# Underglow.net
KiCad netlist of a schematic drawn in Altium Designer
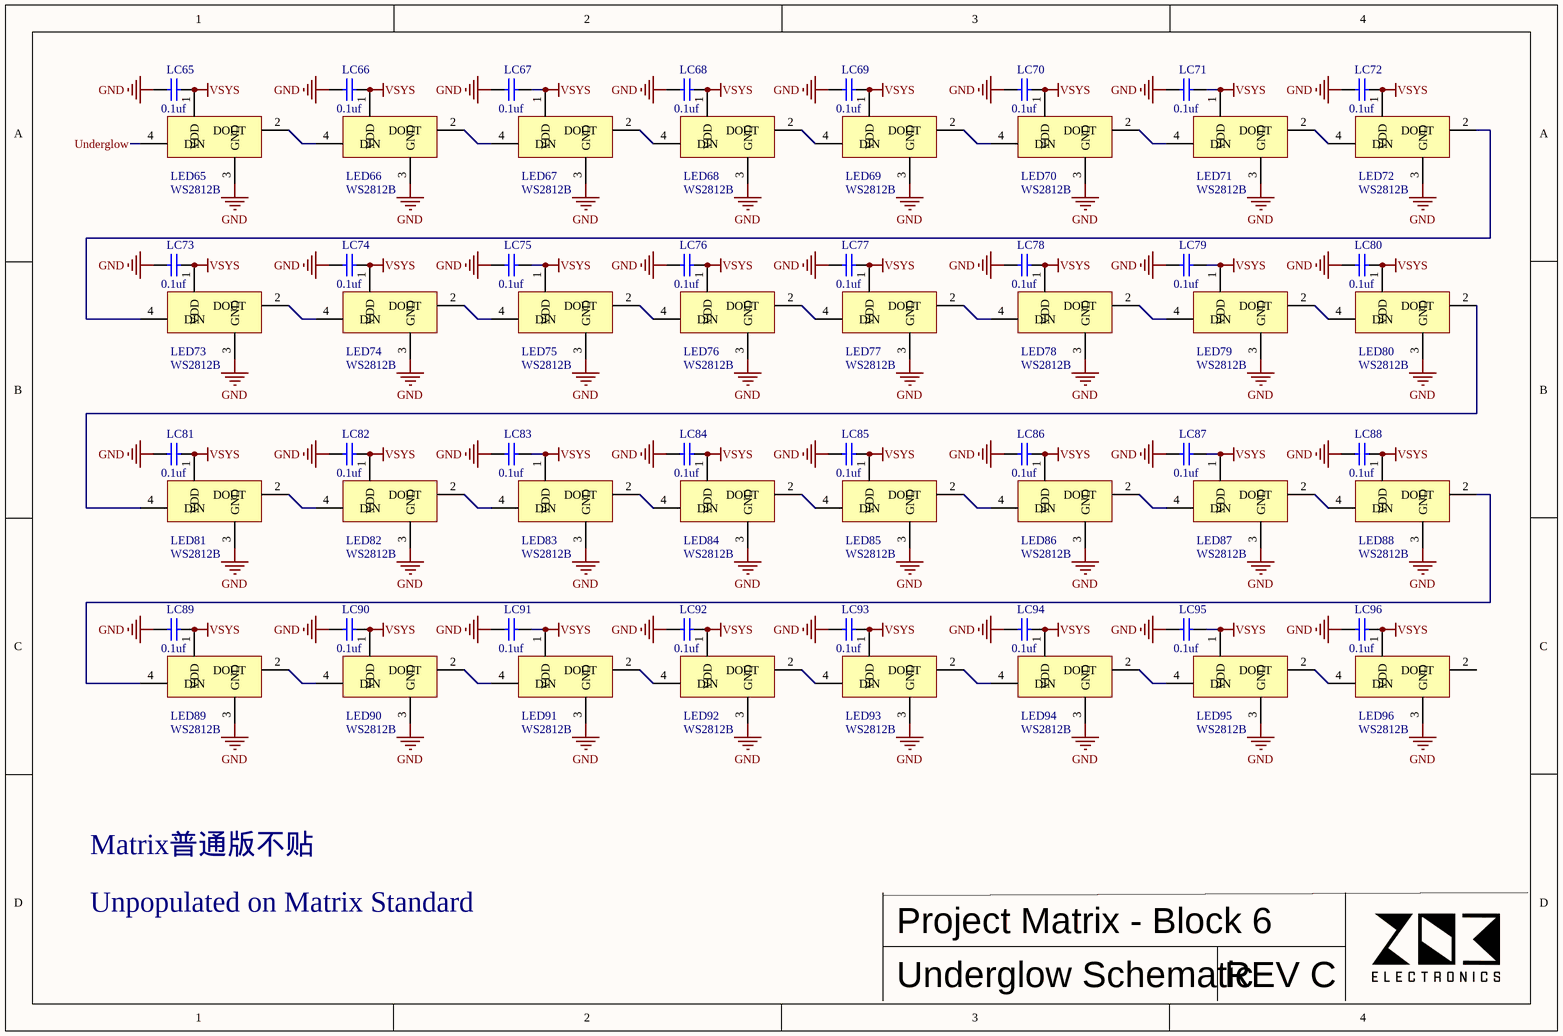
[diagram p0: Underglow.SchDoc]

(export (version "E")
  (design (tool "Eeschema 10.0.6"))
  (components
    (comp (ref "LC65")
      (value "0.1uf")
      (footprint "0603 CAP")
      (description "Capacitor (Semiconductor SIM Model)")
      (fields (field (name "Comment") "Cap Semi") (field (name "PUBLISHER") "Altium Limited"))
      (libsource (lib "Miscellaneous Devices") (part "Cap Semi"))
    )
    (comp (ref "LC66")
      (value "0.1uf")
      (footprint "0603 CAP")
      (description "Capacitor (Semiconductor SIM Model)")
      (fields (field (name "Comment") "Cap Semi") (field (name "PUBLISHER") "Altium Limited"))
      (libsource (lib "Miscellaneous Devices") (part "Cap Semi"))
    )
    (comp (ref "LC67")
      (value "0.1uf")
      (footprint "0603 CAP")
      (description "Capacitor (Semiconductor SIM Model)")
      (fields (field (name "Comment") "Cap Semi") (field (name "PUBLISHER") "Altium Limited"))
      (libsource (lib "Miscellaneous Devices") (part "Cap Semi"))
    )
    (comp (ref "LC68")
      (value "0.1uf")
      (footprint "0603 CAP")
      (description "Capacitor (Semiconductor SIM Model)")
      (fields (field (name "Comment") "Cap Semi") (field (name "PUBLISHER") "Altium Limited"))
      (libsource (lib "Miscellaneous Devices") (part "Cap Semi"))
    )
    (comp (ref "LC69")
      (value "0.1uf")
      (footprint "0603 CAP")
      (description "Capacitor (Semiconductor SIM Model)")
      (fields (field (name "Comment") "Cap Semi") (field (name "PUBLISHER") "Altium Limited"))
      (libsource (lib "Miscellaneous Devices") (part "Cap Semi"))
    )
    (comp (ref "LC70")
      (value "0.1uf")
      (footprint "0603 CAP")
      (description "Capacitor (Semiconductor SIM Model)")
      (fields (field (name "Comment") "Cap Semi") (field (name "PUBLISHER") "Altium Limited"))
      (libsource (lib "Miscellaneous Devices") (part "Cap Semi"))
    )
    (comp (ref "LC71")
      (value "0.1uf")
      (footprint "0603 CAP")
      (description "Capacitor (Semiconductor SIM Model)")
      (fields (field (name "Comment") "Cap Semi") (field (name "PUBLISHER") "Altium Limited"))
      (libsource (lib "Miscellaneous Devices") (part "Cap Semi"))
    )
    (comp (ref "LC72")
      (value "0.1uf")
      (footprint "0603 CAP")
      (description "Capacitor (Semiconductor SIM Model)")
      (fields (field (name "Comment") "Cap Semi") (field (name "PUBLISHER") "Altium Limited"))
      (libsource (lib "Miscellaneous Devices") (part "Cap Semi"))
    )
    (comp (ref "LC73")
      (value "0.1uf")
      (footprint "0603 CAP")
      (description "Capacitor (Semiconductor SIM Model)")
      (fields (field (name "Comment") "Cap Semi") (field (name "PUBLISHER") "Altium Limited"))
      (libsource (lib "Miscellaneous Devices") (part "Cap Semi"))
    )
    (comp (ref "LC74")
      (value "0.1uf")
      (footprint "0603 CAP")
      (description "Capacitor (Semiconductor SIM Model)")
      (fields (field (name "Comment") "Cap Semi") (field (name "PUBLISHER") "Altium Limited"))
      (libsource (lib "Miscellaneous Devices") (part "Cap Semi"))
    )
    (comp (ref "LC75")
      (value "0.1uf")
      (footprint "0603 CAP")
      (description "Capacitor (Semiconductor SIM Model)")
      (fields (field (name "Comment") "Cap Semi") (field (name "PUBLISHER") "Altium Limited"))
      (libsource (lib "Miscellaneous Devices") (part "Cap Semi"))
    )
    (comp (ref "LC76")
      (value "0.1uf")
      (footprint "0603 CAP")
      (description "Capacitor (Semiconductor SIM Model)")
      (fields (field (name "Comment") "Cap Semi") (field (name "PUBLISHER") "Altium Limited"))
      (libsource (lib "Miscellaneous Devices") (part "Cap Semi"))
    )
    (comp (ref "LC77")
      (value "0.1uf")
      (footprint "0603 CAP")
      (description "Capacitor (Semiconductor SIM Model)")
      (fields (field (name "Comment") "Cap Semi") (field (name "PUBLISHER") "Altium Limited"))
      (libsource (lib "Miscellaneous Devices") (part "Cap Semi"))
    )
    (comp (ref "LC78")
      (value "0.1uf")
      (footprint "0603 CAP")
      (description "Capacitor (Semiconductor SIM Model)")
      (fields (field (name "Comment") "Cap Semi") (field (name "PUBLISHER") "Altium Limited"))
      (libsource (lib "Miscellaneous Devices") (part "Cap Semi"))
    )
    (comp (ref "LC79")
      (value "0.1uf")
      (footprint "0603 CAP")
      (description "Capacitor (Semiconductor SIM Model)")
      (fields (field (name "Comment") "Cap Semi") (field (name "PUBLISHER") "Altium Limited"))
      (libsource (lib "Miscellaneous Devices") (part "Cap Semi"))
    )
    (comp (ref "LC80")
      (value "0.1uf")
      (footprint "0603 CAP")
      (description "Capacitor (Semiconductor SIM Model)")
      (fields (field (name "Comment") "Cap Semi") (field (name "PUBLISHER") "Altium Limited"))
      (libsource (lib "Miscellaneous Devices") (part "Cap Semi"))
    )
    (comp (ref "LC81")
      (value "0.1uf")
      (footprint "0603 CAP")
      (description "Capacitor (Semiconductor SIM Model)")
      (fields (field (name "Comment") "Cap Semi") (field (name "PUBLISHER") "Altium Limited"))
      (libsource (lib "Miscellaneous Devices") (part "Cap Semi"))
    )
    (comp (ref "LC82")
      (value "0.1uf")
      (footprint "0603 CAP")
      (description "Capacitor (Semiconductor SIM Model)")
      (fields (field (name "Comment") "Cap Semi") (field (name "PUBLISHER") "Altium Limited"))
      (libsource (lib "Miscellaneous Devices") (part "Cap Semi"))
    )
    (comp (ref "LC83")
      (value "0.1uf")
      (footprint "0603 CAP")
      (description "Capacitor (Semiconductor SIM Model)")
      (fields (field (name "Comment") "Cap Semi") (field (name "PUBLISHER") "Altium Limited"))
      (libsource (lib "Miscellaneous Devices") (part "Cap Semi"))
    )
    (comp (ref "LC84")
      (value "0.1uf")
      (footprint "0603 CAP")
      (description "Capacitor (Semiconductor SIM Model)")
      (fields (field (name "Comment") "Cap Semi") (field (name "PUBLISHER") "Altium Limited"))
      (libsource (lib "Miscellaneous Devices") (part "Cap Semi"))
    )
    (comp (ref "LC85")
      (value "0.1uf")
      (footprint "0603 CAP")
      (description "Capacitor (Semiconductor SIM Model)")
      (fields (field (name "Comment") "Cap Semi") (field (name "PUBLISHER") "Altium Limited"))
      (libsource (lib "Miscellaneous Devices") (part "Cap Semi"))
    )
    (comp (ref "LC86")
      (value "0.1uf")
      (footprint "0603 CAP")
      (description "Capacitor (Semiconductor SIM Model)")
      (fields (field (name "Comment") "Cap Semi") (field (name "PUBLISHER") "Altium Limited"))
      (libsource (lib "Miscellaneous Devices") (part "Cap Semi"))
    )
    (comp (ref "LC87")
      (value "0.1uf")
      (footprint "0603 CAP")
      (description "Capacitor (Semiconductor SIM Model)")
      (fields (field (name "Comment") "Cap Semi") (field (name "PUBLISHER") "Altium Limited"))
      (libsource (lib "Miscellaneous Devices") (part "Cap Semi"))
    )
    (comp (ref "LC88")
      (value "0.1uf")
      (footprint "0603 CAP")
      (description "Capacitor (Semiconductor SIM Model)")
      (fields (field (name "Comment") "Cap Semi") (field (name "PUBLISHER") "Altium Limited"))
      (libsource (lib "Miscellaneous Devices") (part "Cap Semi"))
    )
    (comp (ref "LC89")
      (value "0.1uf")
      (footprint "0603 CAP")
      (description "Capacitor (Semiconductor SIM Model)")
      (fields (field (name "Comment") "Cap Semi") (field (name "PUBLISHER") "Altium Limited"))
      (libsource (lib "Miscellaneous Devices") (part "Cap Semi"))
    )
    (comp (ref "LC90")
      (value "0.1uf")
      (footprint "0603 CAP")
      (description "Capacitor (Semiconductor SIM Model)")
      (fields (field (name "Comment") "Cap Semi") (field (name "PUBLISHER") "Altium Limited"))
      (libsource (lib "Miscellaneous Devices") (part "Cap Semi"))
    )
    (comp (ref "LC91")
      (value "0.1uf")
      (footprint "0603 CAP")
      (description "Capacitor (Semiconductor SIM Model)")
      (fields (field (name "Comment") "Cap Semi") (field (name "PUBLISHER") "Altium Limited"))
      (libsource (lib "Miscellaneous Devices") (part "Cap Semi"))
    )
    (comp (ref "LC92")
      (value "0.1uf")
      (footprint "0603 CAP")
      (description "Capacitor (Semiconductor SIM Model)")
      (fields (field (name "Comment") "Cap Semi") (field (name "PUBLISHER") "Altium Limited"))
      (libsource (lib "Miscellaneous Devices") (part "Cap Semi"))
    )
    (comp (ref "LC93")
      (value "0.1uf")
      (footprint "0603 CAP")
      (description "Capacitor (Semiconductor SIM Model)")
      (fields (field (name "Comment") "Cap Semi") (field (name "PUBLISHER") "Altium Limited"))
      (libsource (lib "Miscellaneous Devices") (part "Cap Semi"))
    )
    (comp (ref "LC94")
      (value "0.1uf")
      (footprint "0603 CAP")
      (description "Capacitor (Semiconductor SIM Model)")
      (fields (field (name "Comment") "Cap Semi") (field (name "PUBLISHER") "Altium Limited"))
      (libsource (lib "Miscellaneous Devices") (part "Cap Semi"))
    )
    (comp (ref "LC95")
      (value "0.1uf")
      (footprint "0603 CAP")
      (description "Capacitor (Semiconductor SIM Model)")
      (fields (field (name "Comment") "Cap Semi") (field (name "PUBLISHER") "Altium Limited"))
      (libsource (lib "Miscellaneous Devices") (part "Cap Semi"))
    )
    (comp (ref "LC96")
      (value "0.1uf")
      (footprint "0603 CAP")
      (description "Capacitor (Semiconductor SIM Model)")
      (fields (field (name "Comment") "Cap Semi") (field (name "PUBLISHER") "Altium Limited"))
      (libsource (lib "Miscellaneous Devices") (part "Cap Semi"))
    )
    (comp (ref "LED65")
      (value "WS2812B")
      (footprint "3210 LED")
      (description "3535")
      (libsource (lib "203") (part "WS2812B"))
    )
    (comp (ref "LED66")
      (value "WS2812B")
      (footprint "3210 LED")
      (description "3535")
      (libsource (lib "203") (part "WS2812B"))
    )
    (comp (ref "LED67")
      (value "WS2812B")
      (footprint "3210 LED")
      (description "3535")
      (libsource (lib "203") (part "WS2812B"))
    )
    (comp (ref "LED68")
      (value "WS2812B")
      (footprint "3210 LED")
      (description "3535")
      (libsource (lib "203") (part "WS2812B"))
    )
    (comp (ref "LED69")
      (value "WS2812B")
      (footprint "3210 LED")
      (description "3535")
      (libsource (lib "203") (part "WS2812B"))
    )
    (comp (ref "LED70")
      (value "WS2812B")
      (footprint "3210 LED")
      (description "3535")
      (libsource (lib "203") (part "WS2812B"))
    )
    (comp (ref "LED71")
      (value "WS2812B")
      (footprint "3210 LED")
      (description "3535")
      (libsource (lib "203") (part "WS2812B"))
    )
    (comp (ref "LED72")
      (value "WS2812B")
      (footprint "3210 LED")
      (description "3535")
      (libsource (lib "203") (part "WS2812B"))
    )
    (comp (ref "LED73")
      (value "WS2812B")
      (footprint "3210 LED")
      (description "3535")
      (libsource (lib "203") (part "WS2812B"))
    )
    (comp (ref "LED74")
      (value "WS2812B")
      (footprint "3210 LED")
      (description "3535")
      (libsource (lib "203") (part "WS2812B"))
    )
    (comp (ref "LED75")
      (value "WS2812B")
      (footprint "3210 LED")
      (description "3535")
      (libsource (lib "203") (part "WS2812B"))
    )
    (comp (ref "LED76")
      (value "WS2812B")
      (footprint "3210 LED")
      (description "3535")
      (libsource (lib "203") (part "WS2812B"))
    )
    (comp (ref "LED77")
      (value "WS2812B")
      (footprint "3210 LED")
      (description "3535")
      (libsource (lib "203") (part "WS2812B"))
    )
    (comp (ref "LED78")
      (value "WS2812B")
      (footprint "3210 LED")
      (description "3535")
      (libsource (lib "203") (part "WS2812B"))
    )
    (comp (ref "LED79")
      (value "WS2812B")
      (footprint "3210 LED")
      (description "3535")
      (libsource (lib "203") (part "WS2812B"))
    )
    (comp (ref "LED80")
      (value "WS2812B")
      (footprint "3210 LED")
      (description "3535")
      (libsource (lib "203") (part "WS2812B"))
    )
    (comp (ref "LED81")
      (value "WS2812B")
      (footprint "3210 LED")
      (description "3535")
      (libsource (lib "203") (part "WS2812B"))
    )
    (comp (ref "LED82")
      (value "WS2812B")
      (footprint "3210 LED")
      (description "3535")
      (libsource (lib "203") (part "WS2812B"))
    )
    (comp (ref "LED83")
      (value "WS2812B")
      (footprint "3210 LED")
      (description "3535")
      (libsource (lib "203") (part "WS2812B"))
    )
    (comp (ref "LED84")
      (value "WS2812B")
      (footprint "3210 LED")
      (description "3535")
      (libsource (lib "203") (part "WS2812B"))
    )
    (comp (ref "LED85")
      (value "WS2812B")
      (footprint "3210 LED")
      (description "3535")
      (libsource (lib "203") (part "WS2812B"))
    )
    (comp (ref "LED86")
      (value "WS2812B")
      (footprint "3210 LED")
      (description "3535")
      (libsource (lib "203") (part "WS2812B"))
    )
    (comp (ref "LED87")
      (value "WS2812B")
      (footprint "3210 LED")
      (description "3535")
      (libsource (lib "203") (part "WS2812B"))
    )
    (comp (ref "LED88")
      (value "WS2812B")
      (footprint "3210 LED")
      (description "3535")
      (libsource (lib "203") (part "WS2812B"))
    )
    (comp (ref "LED89")
      (value "WS2812B")
      (footprint "3210 LED")
      (description "3535")
      (libsource (lib "203") (part "WS2812B"))
    )
    (comp (ref "LED90")
      (value "WS2812B")
      (footprint "3210 LED")
      (description "3535")
      (libsource (lib "203") (part "WS2812B"))
    )
    (comp (ref "LED91")
      (value "WS2812B")
      (footprint "3210 LED")
      (description "3535")
      (libsource (lib "203") (part "WS2812B"))
    )
    (comp (ref "LED92")
      (value "WS2812B")
      (footprint "3210 LED")
      (description "3535")
      (libsource (lib "203") (part "WS2812B"))
    )
    (comp (ref "LED93")
      (value "WS2812B")
      (footprint "3210 LED")
      (description "3535")
      (libsource (lib "203") (part "WS2812B"))
    )
    (comp (ref "LED94")
      (value "WS2812B")
      (footprint "3210 LED")
      (description "3535")
      (libsource (lib "203") (part "WS2812B"))
    )
    (comp (ref "LED95")
      (value "WS2812B")
      (footprint "3210 LED")
      (description "3535")
      (libsource (lib "203") (part "WS2812B"))
    )
    (comp (ref "LED96")
      (value "WS2812B")
      (footprint "3210 LED")
      (description "3535")
      (libsource (lib "203") (part "WS2812B"))
    )
  )
  (nets
    (net (code "1") (name "/Underglow") (class "Default")
      (node (ref "LED65") (pin "4") (pinfunction "DIN_4") (pintype "passive"))
    )
    (net (code "2") (name "GND") (class "Default")
      (node (ref "LC65") (pin "1") (pinfunction "1_1") (pintype "passive"))
      (node (ref "LC66") (pin "1") (pinfunction "1_1") (pintype "passive"))
      (node (ref "LC67") (pin "1") (pinfunction "1_1") (pintype "passive"))
      (node (ref "LC68") (pin "1") (pinfunction "1_1") (pintype "passive"))
      (node (ref "LC69") (pin "1") (pinfunction "1_1") (pintype "passive"))
      (node (ref "LC70") (pin "1") (pinfunction "1_1") (pintype "passive"))
      (node (ref "LC71") (pin "1") (pinfunction "1_1") (pintype "passive"))
      (node (ref "LC72") (pin "1") (pinfunction "1_1") (pintype "passive"))
      (node (ref "LC73") (pin "1") (pinfunction "1_1") (pintype "passive"))
      (node (ref "LC74") (pin "1") (pinfunction "1_1") (pintype "passive"))
      (node (ref "LC75") (pin "1") (pinfunction "1_1") (pintype "passive"))
      (node (ref "LC76") (pin "1") (pinfunction "1_1") (pintype "passive"))
      (node (ref "LC77") (pin "1") (pinfunction "1_1") (pintype "passive"))
      (node (ref "LC78") (pin "1") (pinfunction "1_1") (pintype "passive"))
      (node (ref "LC79") (pin "1") (pinfunction "1_1") (pintype "passive"))
      (node (ref "LC80") (pin "1") (pinfunction "1_1") (pintype "passive"))
      (node (ref "LC81") (pin "1") (pinfunction "1_1") (pintype "passive"))
      (node (ref "LC82") (pin "1") (pinfunction "1_1") (pintype "passive"))
      (node (ref "LC83") (pin "1") (pinfunction "1_1") (pintype "passive"))
      (node (ref "LC84") (pin "1") (pinfunction "1_1") (pintype "passive"))
      (node (ref "LC85") (pin "1") (pinfunction "1_1") (pintype "passive"))
      (node (ref "LC86") (pin "1") (pinfunction "1_1") (pintype "passive"))
      (node (ref "LC87") (pin "1") (pinfunction "1_1") (pintype "passive"))
      (node (ref "LC88") (pin "1") (pinfunction "1_1") (pintype "passive"))
      (node (ref "LC89") (pin "1") (pinfunction "1_1") (pintype "passive"))
      (node (ref "LC90") (pin "1") (pinfunction "1_1") (pintype "passive"))
      (node (ref "LC91") (pin "1") (pinfunction "1_1") (pintype "passive"))
      (node (ref "LC92") (pin "1") (pinfunction "1_1") (pintype "passive"))
      (node (ref "LC93") (pin "1") (pinfunction "1_1") (pintype "passive"))
      (node (ref "LC94") (pin "1") (pinfunction "1_1") (pintype "passive"))
      (node (ref "LC95") (pin "1") (pinfunction "1_1") (pintype "passive"))
      (node (ref "LC96") (pin "1") (pinfunction "1_1") (pintype "passive"))
      (node (ref "LED65") (pin "3") (pinfunction "GND_3") (pintype "passive"))
      (node (ref "LED66") (pin "3") (pinfunction "GND_3") (pintype "passive"))
      (node (ref "LED67") (pin "3") (pinfunction "GND_3") (pintype "passive"))
      (node (ref "LED68") (pin "3") (pinfunction "GND_3") (pintype "passive"))
      (node (ref "LED69") (pin "3") (pinfunction "GND_3") (pintype "passive"))
      (node (ref "LED70") (pin "3") (pinfunction "GND_3") (pintype "passive"))
      (node (ref "LED71") (pin "3") (pinfunction "GND_3") (pintype "passive"))
      (node (ref "LED72") (pin "3") (pinfunction "GND_3") (pintype "passive"))
      (node (ref "LED73") (pin "3") (pinfunction "GND_3") (pintype "passive"))
      (node (ref "LED74") (pin "3") (pinfunction "GND_3") (pintype "passive"))
      (node (ref "LED75") (pin "3") (pinfunction "GND_3") (pintype "passive"))
      (node (ref "LED76") (pin "3") (pinfunction "GND_3") (pintype "passive"))
      (node (ref "LED77") (pin "3") (pinfunction "GND_3") (pintype "passive"))
      (node (ref "LED78") (pin "3") (pinfunction "GND_3") (pintype "passive"))
      (node (ref "LED79") (pin "3") (pinfunction "GND_3") (pintype "passive"))
      (node (ref "LED80") (pin "3") (pinfunction "GND_3") (pintype "passive"))
      (node (ref "LED81") (pin "3") (pinfunction "GND_3") (pintype "passive"))
      (node (ref "LED82") (pin "3") (pinfunction "GND_3") (pintype "passive"))
      (node (ref "LED83") (pin "3") (pinfunction "GND_3") (pintype "passive"))
      (node (ref "LED84") (pin "3") (pinfunction "GND_3") (pintype "passive"))
      (node (ref "LED85") (pin "3") (pinfunction "GND_3") (pintype "passive"))
      (node (ref "LED86") (pin "3") (pinfunction "GND_3") (pintype "passive"))
      (node (ref "LED87") (pin "3") (pinfunction "GND_3") (pintype "passive"))
      (node (ref "LED88") (pin "3") (pinfunction "GND_3") (pintype "passive"))
      (node (ref "LED89") (pin "3") (pinfunction "GND_3") (pintype "passive"))
      (node (ref "LED90") (pin "3") (pinfunction "GND_3") (pintype "passive"))
      (node (ref "LED91") (pin "3") (pinfunction "GND_3") (pintype "passive"))
      (node (ref "LED92") (pin "3") (pinfunction "GND_3") (pintype "passive"))
      (node (ref "LED93") (pin "3") (pinfunction "GND_3") (pintype "passive"))
      (node (ref "LED94") (pin "3") (pinfunction "GND_3") (pintype "passive"))
      (node (ref "LED95") (pin "3") (pinfunction "GND_3") (pintype "passive"))
      (node (ref "LED96") (pin "3") (pinfunction "GND_3") (pintype "passive"))
    )
    (net (code "3") (name "Net-(LED65-DOUT)") (class "Default")
      (node (ref "LED65") (pin "2") (pinfunction "DOUT_2") (pintype "passive"))
      (node (ref "LED66") (pin "4") (pinfunction "DIN_4") (pintype "passive"))
    )
    (net (code "4") (name "Net-(LED66-DOUT)") (class "Default")
      (node (ref "LED66") (pin "2") (pinfunction "DOUT_2") (pintype "passive"))
      (node (ref "LED67") (pin "4") (pinfunction "DIN_4") (pintype "passive"))
    )
    (net (code "5") (name "Net-(LED67-DOUT)") (class "Default")
      (node (ref "LED67") (pin "2") (pinfunction "DOUT_2") (pintype "passive"))
      (node (ref "LED68") (pin "4") (pinfunction "DIN_4") (pintype "passive"))
    )
    (net (code "6") (name "Net-(LED68-DOUT)") (class "Default")
      (node (ref "LED68") (pin "2") (pinfunction "DOUT_2") (pintype "passive"))
      (node (ref "LED69") (pin "4") (pinfunction "DIN_4") (pintype "passive"))
    )
    (net (code "7") (name "Net-(LED69-DOUT)") (class "Default")
      (node (ref "LED69") (pin "2") (pinfunction "DOUT_2") (pintype "passive"))
      (node (ref "LED70") (pin "4") (pinfunction "DIN_4") (pintype "passive"))
    )
    (net (code "8") (name "Net-(LED70-DOUT)") (class "Default")
      (node (ref "LED70") (pin "2") (pinfunction "DOUT_2") (pintype "passive"))
      (node (ref "LED71") (pin "4") (pinfunction "DIN_4") (pintype "passive"))
    )
    (net (code "9") (name "Net-(LED71-DOUT)") (class "Default")
      (node (ref "LED71") (pin "2") (pinfunction "DOUT_2") (pintype "passive"))
      (node (ref "LED72") (pin "4") (pinfunction "DIN_4") (pintype "passive"))
    )
    (net (code "10") (name "Net-(LED72-DOUT)") (class "Default")
      (node (ref "LED72") (pin "2") (pinfunction "DOUT_2") (pintype "passive"))
      (node (ref "LED73") (pin "4") (pinfunction "DIN_4") (pintype "passive"))
    )
    (net (code "11") (name "Net-(LED73-DOUT)") (class "Default")
      (node (ref "LED73") (pin "2") (pinfunction "DOUT_2") (pintype "passive"))
      (node (ref "LED74") (pin "4") (pinfunction "DIN_4") (pintype "passive"))
    )
    (net (code "12") (name "Net-(LED74-DOUT)") (class "Default")
      (node (ref "LED74") (pin "2") (pinfunction "DOUT_2") (pintype "passive"))
      (node (ref "LED75") (pin "4") (pinfunction "DIN_4") (pintype "passive"))
    )
    (net (code "13") (name "Net-(LED75-DOUT)") (class "Default")
      (node (ref "LED75") (pin "2") (pinfunction "DOUT_2") (pintype "passive"))
      (node (ref "LED76") (pin "4") (pinfunction "DIN_4") (pintype "passive"))
    )
    (net (code "14") (name "Net-(LED76-DOUT)") (class "Default")
      (node (ref "LED76") (pin "2") (pinfunction "DOUT_2") (pintype "passive"))
      (node (ref "LED77") (pin "4") (pinfunction "DIN_4") (pintype "passive"))
    )
    (net (code "15") (name "Net-(LED77-DOUT)") (class "Default")
      (node (ref "LED77") (pin "2") (pinfunction "DOUT_2") (pintype "passive"))
      (node (ref "LED78") (pin "4") (pinfunction "DIN_4") (pintype "passive"))
    )
    (net (code "16") (name "Net-(LED78-DOUT)") (class "Default")
      (node (ref "LED78") (pin "2") (pinfunction "DOUT_2") (pintype "passive"))
      (node (ref "LED79") (pin "4") (pinfunction "DIN_4") (pintype "passive"))
    )
    (net (code "17") (name "Net-(LED79-DOUT)") (class "Default")
      (node (ref "LED79") (pin "2") (pinfunction "DOUT_2") (pintype "passive"))
      (node (ref "LED80") (pin "4") (pinfunction "DIN_4") (pintype "passive"))
    )
    (net (code "18") (name "Net-(LED80-DOUT)") (class "Default")
      (node (ref "LED80") (pin "2") (pinfunction "DOUT_2") (pintype "passive"))
      (node (ref "LED81") (pin "4") (pinfunction "DIN_4") (pintype "passive"))
    )
    (net (code "19") (name "Net-(LED81-DOUT)") (class "Default")
      (node (ref "LED81") (pin "2") (pinfunction "DOUT_2") (pintype "passive"))
      (node (ref "LED82") (pin "4") (pinfunction "DIN_4") (pintype "passive"))
    )
    (net (code "20") (name "Net-(LED82-DOUT)") (class "Default")
      (node (ref "LED82") (pin "2") (pinfunction "DOUT_2") (pintype "passive"))
      (node (ref "LED83") (pin "4") (pinfunction "DIN_4") (pintype "passive"))
    )
    (net (code "21") (name "Net-(LED83-DOUT)") (class "Default")
      (node (ref "LED83") (pin "2") (pinfunction "DOUT_2") (pintype "passive"))
      (node (ref "LED84") (pin "4") (pinfunction "DIN_4") (pintype "passive"))
    )
    (net (code "22") (name "Net-(LED84-DOUT)") (class "Default")
      (node (ref "LED84") (pin "2") (pinfunction "DOUT_2") (pintype "passive"))
      (node (ref "LED85") (pin "4") (pinfunction "DIN_4") (pintype "passive"))
    )
    (net (code "23") (name "Net-(LED85-DOUT)") (class "Default")
      (node (ref "LED85") (pin "2") (pinfunction "DOUT_2") (pintype "passive"))
      (node (ref "LED86") (pin "4") (pinfunction "DIN_4") (pintype "passive"))
    )
    (net (code "24") (name "Net-(LED86-DOUT)") (class "Default")
      (node (ref "LED86") (pin "2") (pinfunction "DOUT_2") (pintype "passive"))
      (node (ref "LED87") (pin "4") (pinfunction "DIN_4") (pintype "passive"))
    )
    (net (code "25") (name "Net-(LED87-DOUT)") (class "Default")
      (node (ref "LED87") (pin "2") (pinfunction "DOUT_2") (pintype "passive"))
      (node (ref "LED88") (pin "4") (pinfunction "DIN_4") (pintype "passive"))
    )
    (net (code "26") (name "Net-(LED88-DOUT)") (class "Default")
      (node (ref "LED88") (pin "2") (pinfunction "DOUT_2") (pintype "passive"))
      (node (ref "LED89") (pin "4") (pinfunction "DIN_4") (pintype "passive"))
    )
    (net (code "27") (name "Net-(LED89-DOUT)") (class "Default")
      (node (ref "LED89") (pin "2") (pinfunction "DOUT_2") (pintype "passive"))
      (node (ref "LED90") (pin "4") (pinfunction "DIN_4") (pintype "passive"))
    )
    (net (code "28") (name "Net-(LED90-DOUT)") (class "Default")
      (node (ref "LED90") (pin "2") (pinfunction "DOUT_2") (pintype "passive"))
      (node (ref "LED91") (pin "4") (pinfunction "DIN_4") (pintype "passive"))
    )
    (net (code "29") (name "Net-(LED91-DOUT)") (class "Default")
      (node (ref "LED91") (pin "2") (pinfunction "DOUT_2") (pintype "passive"))
      (node (ref "LED92") (pin "4") (pinfunction "DIN_4") (pintype "passive"))
    )
    (net (code "30") (name "Net-(LED92-DOUT)") (class "Default")
      (node (ref "LED92") (pin "2") (pinfunction "DOUT_2") (pintype "passive"))
      (node (ref "LED93") (pin "4") (pinfunction "DIN_4") (pintype "passive"))
    )
    (net (code "31") (name "Net-(LED93-DOUT)") (class "Default")
      (node (ref "LED93") (pin "2") (pinfunction "DOUT_2") (pintype "passive"))
      (node (ref "LED94") (pin "4") (pinfunction "DIN_4") (pintype "passive"))
    )
    (net (code "32") (name "Net-(LED94-DOUT)") (class "Default")
      (node (ref "LED94") (pin "2") (pinfunction "DOUT_2") (pintype "passive"))
      (node (ref "LED95") (pin "4") (pinfunction "DIN_4") (pintype "passive"))
    )
    (net (code "33") (name "Net-(LED95-DOUT)") (class "Default")
      (node (ref "LED95") (pin "2") (pinfunction "DOUT_2") (pintype "passive"))
      (node (ref "LED96") (pin "4") (pinfunction "DIN_4") (pintype "passive"))
    )
    (net (code "34") (name "VSYS") (class "Default")
      (node (ref "LC65") (pin "2") (pinfunction "2_2") (pintype "passive"))
      (node (ref "LC66") (pin "2") (pinfunction "2_2") (pintype "passive"))
      (node (ref "LC67") (pin "2") (pinfunction "2_2") (pintype "passive"))
      (node (ref "LC68") (pin "2") (pinfunction "2_2") (pintype "passive"))
      (node (ref "LC69") (pin "2") (pinfunction "2_2") (pintype "passive"))
      (node (ref "LC70") (pin "2") (pinfunction "2_2") (pintype "passive"))
      (node (ref "LC71") (pin "2") (pinfunction "2_2") (pintype "passive"))
      (node (ref "LC72") (pin "2") (pinfunction "2_2") (pintype "passive"))
      (node (ref "LC73") (pin "2") (pinfunction "2_2") (pintype "passive"))
      (node (ref "LC74") (pin "2") (pinfunction "2_2") (pintype "passive"))
      (node (ref "LC75") (pin "2") (pinfunction "2_2") (pintype "passive"))
      (node (ref "LC76") (pin "2") (pinfunction "2_2") (pintype "passive"))
      (node (ref "LC77") (pin "2") (pinfunction "2_2") (pintype "passive"))
      (node (ref "LC78") (pin "2") (pinfunction "2_2") (pintype "passive"))
      (node (ref "LC79") (pin "2") (pinfunction "2_2") (pintype "passive"))
      (node (ref "LC80") (pin "2") (pinfunction "2_2") (pintype "passive"))
      (node (ref "LC81") (pin "2") (pinfunction "2_2") (pintype "passive"))
      (node (ref "LC82") (pin "2") (pinfunction "2_2") (pintype "passive"))
      (node (ref "LC83") (pin "2") (pinfunction "2_2") (pintype "passive"))
      (node (ref "LC84") (pin "2") (pinfunction "2_2") (pintype "passive"))
      (node (ref "LC85") (pin "2") (pinfunction "2_2") (pintype "passive"))
      (node (ref "LC86") (pin "2") (pinfunction "2_2") (pintype "passive"))
      (node (ref "LC87") (pin "2") (pinfunction "2_2") (pintype "passive"))
      (node (ref "LC88") (pin "2") (pinfunction "2_2") (pintype "passive"))
      (node (ref "LC89") (pin "2") (pinfunction "2_2") (pintype "passive"))
      (node (ref "LC90") (pin "2") (pinfunction "2_2") (pintype "passive"))
      (node (ref "LC91") (pin "2") (pinfunction "2_2") (pintype "passive"))
      (node (ref "LC92") (pin "2") (pinfunction "2_2") (pintype "passive"))
      (node (ref "LC93") (pin "2") (pinfunction "2_2") (pintype "passive"))
      (node (ref "LC94") (pin "2") (pinfunction "2_2") (pintype "passive"))
      (node (ref "LC95") (pin "2") (pinfunction "2_2") (pintype "passive"))
      (node (ref "LC96") (pin "2") (pinfunction "2_2") (pintype "passive"))
      (node (ref "LED65") (pin "1") (pinfunction "VDD_1") (pintype "passive"))
      (node (ref "LED66") (pin "1") (pinfunction "VDD_1") (pintype "passive"))
      (node (ref "LED67") (pin "1") (pinfunction "VDD_1") (pintype "passive"))
      (node (ref "LED68") (pin "1") (pinfunction "VDD_1") (pintype "passive"))
      (node (ref "LED69") (pin "1") (pinfunction "VDD_1") (pintype "passive"))
      (node (ref "LED70") (pin "1") (pinfunction "VDD_1") (pintype "passive"))
      (node (ref "LED71") (pin "1") (pinfunction "VDD_1") (pintype "passive"))
      (node (ref "LED72") (pin "1") (pinfunction "VDD_1") (pintype "passive"))
      (node (ref "LED73") (pin "1") (pinfunction "VDD_1") (pintype "passive"))
      (node (ref "LED74") (pin "1") (pinfunction "VDD_1") (pintype "passive"))
      (node (ref "LED75") (pin "1") (pinfunction "VDD_1") (pintype "passive"))
      (node (ref "LED76") (pin "1") (pinfunction "VDD_1") (pintype "passive"))
      (node (ref "LED77") (pin "1") (pinfunction "VDD_1") (pintype "passive"))
      (node (ref "LED78") (pin "1") (pinfunction "VDD_1") (pintype "passive"))
      (node (ref "LED79") (pin "1") (pinfunction "VDD_1") (pintype "passive"))
      (node (ref "LED80") (pin "1") (pinfunction "VDD_1") (pintype "passive"))
      (node (ref "LED81") (pin "1") (pinfunction "VDD_1") (pintype "passive"))
      (node (ref "LED82") (pin "1") (pinfunction "VDD_1") (pintype "passive"))
      (node (ref "LED83") (pin "1") (pinfunction "VDD_1") (pintype "passive"))
      (node (ref "LED84") (pin "1") (pinfunction "VDD_1") (pintype "passive"))
      (node (ref "LED85") (pin "1") (pinfunction "VDD_1") (pintype "passive"))
      (node (ref "LED86") (pin "1") (pinfunction "VDD_1") (pintype "passive"))
      (node (ref "LED87") (pin "1") (pinfunction "VDD_1") (pintype "passive"))
      (node (ref "LED88") (pin "1") (pinfunction "VDD_1") (pintype "passive"))
      (node (ref "LED89") (pin "1") (pinfunction "VDD_1") (pintype "passive"))
      (node (ref "LED90") (pin "1") (pinfunction "VDD_1") (pintype "passive"))
      (node (ref "LED91") (pin "1") (pinfunction "VDD_1") (pintype "passive"))
      (node (ref "LED92") (pin "1") (pinfunction "VDD_1") (pintype "passive"))
      (node (ref "LED93") (pin "1") (pinfunction "VDD_1") (pintype "passive"))
      (node (ref "LED94") (pin "1") (pinfunction "VDD_1") (pintype "passive"))
      (node (ref "LED95") (pin "1") (pinfunction "VDD_1") (pintype "passive"))
      (node (ref "LED96") (pin "1") (pinfunction "VDD_1") (pintype "passive"))
    )
    (net (code "35") (name "unconnected-(LED96-DOUT-Pad2)") (class "Default")
      (node (ref "LED96") (pin "2") (pinfunction "DOUT_2") (pintype "passive"))
    )
  )
)
